# RGB_SMD.net
KiCad netlist of a schematic drawn in EAGLE
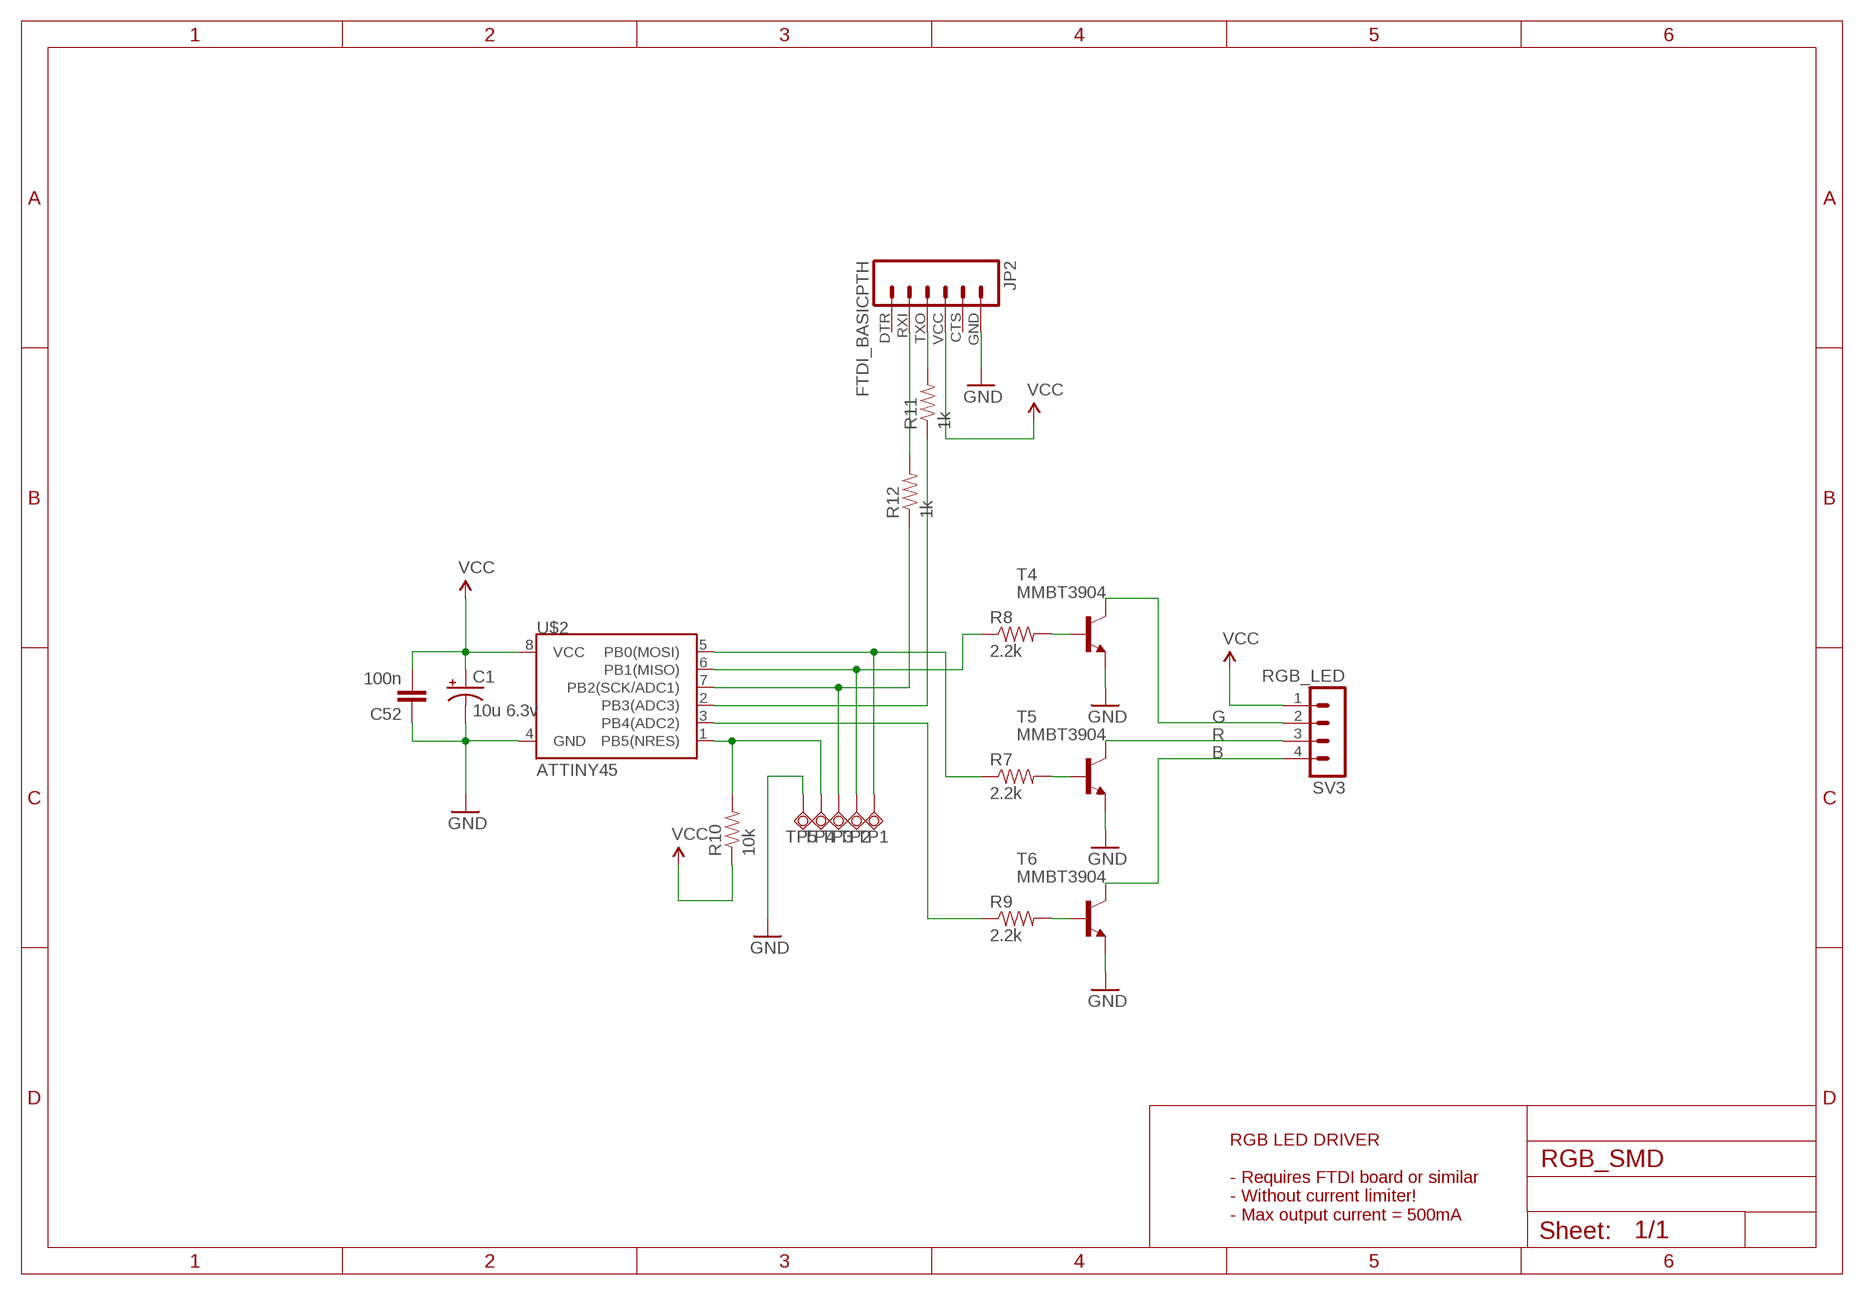
[diagram p0: schematic, sheet 1]

(export (version "E")
  (design (tool "Eeschema 10.0.6"))
  (components
    (comp (ref "C1")
      (value "10u 6.3v")
      (footprint "eagle-import:EIA3216")
      (libsource (lib "eagle-import") (part "CAP_POL1206"))
    )
    (comp (ref "C52")
      (value "100n")
      (footprint "eagle-import:0805")
      (libsource (lib "eagle-import") (part "CAP0805"))
    )
    (comp (ref "JP2")
      (value "FTDI_BASICPTH")
      (footprint "eagle-import:FTDI_BASIC")
      (libsource (lib "eagle-import") (part "FTDI_BASICPTH"))
    )
    (comp (ref "R7")
      (value "2.2k")
      (footprint "eagle-import:0805")
      (libsource (lib "eagle-import") (part "RESISTOR0805-RES"))
    )
    (comp (ref "R8")
      (value "2.2k")
      (footprint "eagle-import:0805")
      (libsource (lib "eagle-import") (part "RESISTOR0805-RES"))
    )
    (comp (ref "R9")
      (value "2.2k")
      (footprint "eagle-import:0805")
      (libsource (lib "eagle-import") (part "RESISTOR0805-RES"))
    )
    (comp (ref "R10")
      (value "10k")
      (footprint "eagle-import:0805")
      (libsource (lib "eagle-import") (part "RESISTOR0805-RES"))
    )
    (comp (ref "R11")
      (value "1k")
      (footprint "eagle-import:0805")
      (libsource (lib "eagle-import") (part "RESISTOR0805-RES"))
    )
    (comp (ref "R12")
      (value "1k")
      (footprint "eagle-import:0805")
      (libsource (lib "eagle-import") (part "RESISTOR0805-RES"))
    )
    (comp (ref "SV3")
      (value "RGB_LED")
      (footprint "eagle-import:MA04-1")
      (libsource (lib "eagle-import") (part "MA04-1"))
    )
    (comp (ref "T4")
      (value "MMBT3904")
      (footprint "eagle-import:SOT23-BEC")
      (libsource (lib "eagle-import") (part "-NPN-SOT23-BECMMBT3904LT1"))
    )
    (comp (ref "T5")
      (value "MMBT3904")
      (footprint "eagle-import:SOT23-BEC")
      (libsource (lib "eagle-import") (part "-NPN-SOT23-BECMMBT3904LT1"))
    )
    (comp (ref "T6")
      (value "MMBT3904")
      (footprint "eagle-import:SOT23-BEC")
      (libsource (lib "eagle-import") (part "-NPN-SOT23-BECMMBT3904LT1"))
    )
    (comp (ref "TP1")
      (value "TPSQTP16SQ")
      (footprint "eagle-import:TP16SQ")
      (libsource (lib "eagle-import") (part "TPSQTP16SQ"))
    )
    (comp (ref "TP2")
      (value "TPSQTP16SQ")
      (footprint "eagle-import:TP16SQ")
      (libsource (lib "eagle-import") (part "TPSQTP16SQ"))
    )
    (comp (ref "TP3")
      (value "TPSQTP16SQ")
      (footprint "eagle-import:TP16SQ")
      (libsource (lib "eagle-import") (part "TPSQTP16SQ"))
    )
    (comp (ref "TP4")
      (value "TPSQTP16SQ")
      (footprint "eagle-import:TP16SQ")
      (libsource (lib "eagle-import") (part "TPSQTP16SQ"))
    )
    (comp (ref "TP5")
      (value "TPSQTP16SQ")
      (footprint "eagle-import:TP16SQ")
      (libsource (lib "eagle-import") (part "TPSQTP16SQ"))
    )
    (comp (ref "U$2")
      (value "ATTINY45")
      (footprint "eagle-import:SO08-EIAJ")
      (libsource (lib "eagle-import") (part "ATTINY45"))
    )
  )
  (nets
    (net (code "1") (name "/B") (class "Default")
      (node (ref "SV3") (pin "4") (pinfunction "4_4") (pintype "passive"))
      (node (ref "T6") (pin "C") (pinfunction "C_C") (pintype "passive"))
    )
    (net (code "2") (name "/G") (class "Default")
      (node (ref "SV3") (pin "2") (pinfunction "2_2") (pintype "passive"))
      (node (ref "T4") (pin "C") (pinfunction "C_C") (pintype "passive"))
    )
    (net (code "3") (name "/R") (class "Default")
      (node (ref "SV3") (pin "3") (pinfunction "3_3") (pintype "passive"))
      (node (ref "T5") (pin "C") (pinfunction "C_C") (pintype "passive"))
    )
    (net (code "4") (name "GND") (class "Default")
      (node (ref "C1") (pin "C") (pinfunction "-_C") (pintype "passive"))
      (node (ref "C52") (pin "1") (pinfunction "1_1") (pintype "passive"))
      (node (ref "JP2") (pin "GND") (pinfunction "6_GND") (pintype "passive"))
      (node (ref "T4") (pin "E") (pinfunction "E_E") (pintype "passive"))
      (node (ref "T5") (pin "E") (pinfunction "E_E") (pintype "passive"))
      (node (ref "T6") (pin "E") (pinfunction "E_E") (pintype "passive"))
      (node (ref "TP5") (pin "TP") (pinfunction "TP_TP") (pintype "input"))
      (node (ref "U$2") (pin "4") (pinfunction "GND_4") (pintype "bidirectional"))
    )
    (net (code "5") (name "Net-(JP2-2)") (class "Default")
      (node (ref "JP2") (pin "RXI") (pinfunction "2_RXI") (pintype "passive"))
      (node (ref "R12") (pin "2") (pinfunction "2_2") (pintype "passive"))
    )
    (net (code "6") (name "Net-(JP2-3)") (class "Default")
      (node (ref "JP2") (pin "TXO") (pinfunction "3_TXO") (pintype "passive"))
      (node (ref "R11") (pin "2") (pinfunction "2_2") (pintype "passive"))
    )
    (net (code "7") (name "Net-(R7-Pad2)") (class "Default")
      (node (ref "R7") (pin "2") (pinfunction "2_2") (pintype "passive"))
      (node (ref "T5") (pin "B") (pinfunction "B_B") (pintype "passive"))
    )
    (net (code "8") (name "Net-(R8-Pad2)") (class "Default")
      (node (ref "R8") (pin "2") (pinfunction "2_2") (pintype "passive"))
      (node (ref "T4") (pin "B") (pinfunction "B_B") (pintype "passive"))
    )
    (net (code "9") (name "Net-(R9-Pad2)") (class "Default")
      (node (ref "R9") (pin "2") (pinfunction "2_2") (pintype "passive"))
      (node (ref "T6") (pin "B") (pinfunction "B_B") (pintype "passive"))
    )
    (net (code "10") (name "Net-(U$2-PB0(MOSI))") (class "Default")
      (node (ref "R7") (pin "1") (pinfunction "1_1") (pintype "passive"))
      (node (ref "TP1") (pin "TP") (pinfunction "TP_TP") (pintype "input"))
      (node (ref "U$2") (pin "5") (pinfunction "PB0(MOSI)_5") (pintype "bidirectional"))
    )
    (net (code "11") (name "Net-(U$2-PB1(MISO))") (class "Default")
      (node (ref "R8") (pin "1") (pinfunction "1_1") (pintype "passive"))
      (node (ref "TP2") (pin "TP") (pinfunction "TP_TP") (pintype "input"))
      (node (ref "U$2") (pin "6") (pinfunction "PB1(MISO)_6") (pintype "bidirectional"))
    )
    (net (code "12") (name "Net-(U$2-PB2(SCK{slash}ADC1))") (class "Default")
      (node (ref "R12") (pin "1") (pinfunction "1_1") (pintype "passive"))
      (node (ref "TP3") (pin "TP") (pinfunction "TP_TP") (pintype "input"))
      (node (ref "U$2") (pin "7") (pinfunction "PB2(SCK/ADC1)_7") (pintype "bidirectional"))
    )
    (net (code "13") (name "Net-(U$2-PB3(ADC3))") (class "Default")
      (node (ref "R11") (pin "1") (pinfunction "1_1") (pintype "passive"))
      (node (ref "U$2") (pin "2") (pinfunction "PB3(ADC3)_2") (pintype "bidirectional"))
    )
    (net (code "14") (name "Net-(U$2-PB4(ADC2))") (class "Default")
      (node (ref "R9") (pin "1") (pinfunction "1_1") (pintype "passive"))
      (node (ref "U$2") (pin "3") (pinfunction "PB4(ADC2)_3") (pintype "bidirectional"))
    )
    (net (code "15") (name "Net-(U$2-PB5(NRES))") (class "Default")
      (node (ref "R10") (pin "2") (pinfunction "2_2") (pintype "passive"))
      (node (ref "TP4") (pin "TP") (pinfunction "TP_TP") (pintype "input"))
      (node (ref "U$2") (pin "1") (pinfunction "PB5(NRES)_1") (pintype "bidirectional"))
    )
    (net (code "16") (name "VCC") (class "Default")
      (node (ref "C1") (pin "A") (pinfunction "+_A") (pintype "passive"))
      (node (ref "C52") (pin "2") (pinfunction "2_2") (pintype "passive"))
      (node (ref "JP2") (pin "VCC") (pinfunction "4_VCC") (pintype "passive"))
      (node (ref "R10") (pin "1") (pinfunction "1_1") (pintype "passive"))
      (node (ref "SV3") (pin "1") (pinfunction "1_1") (pintype "passive"))
      (node (ref "U$2") (pin "8") (pinfunction "VCC_8") (pintype "bidirectional"))
    )
    (net (code "17") (name "unconnected-(JP2-1-PadDTR)") (class "Default")
      (node (ref "JP2") (pin "DTR") (pinfunction "1_DTR") (pintype "passive"))
    )
    (net (code "18") (name "unconnected-(JP2-5-PadCTS)") (class "Default")
      (node (ref "JP2") (pin "CTS") (pinfunction "5_CTS") (pintype "passive"))
    )
  )
)
